# Shutdown_2019_v1_1_BrakeLight.net
KiCad netlist of a schematic drawn in Altium Designer
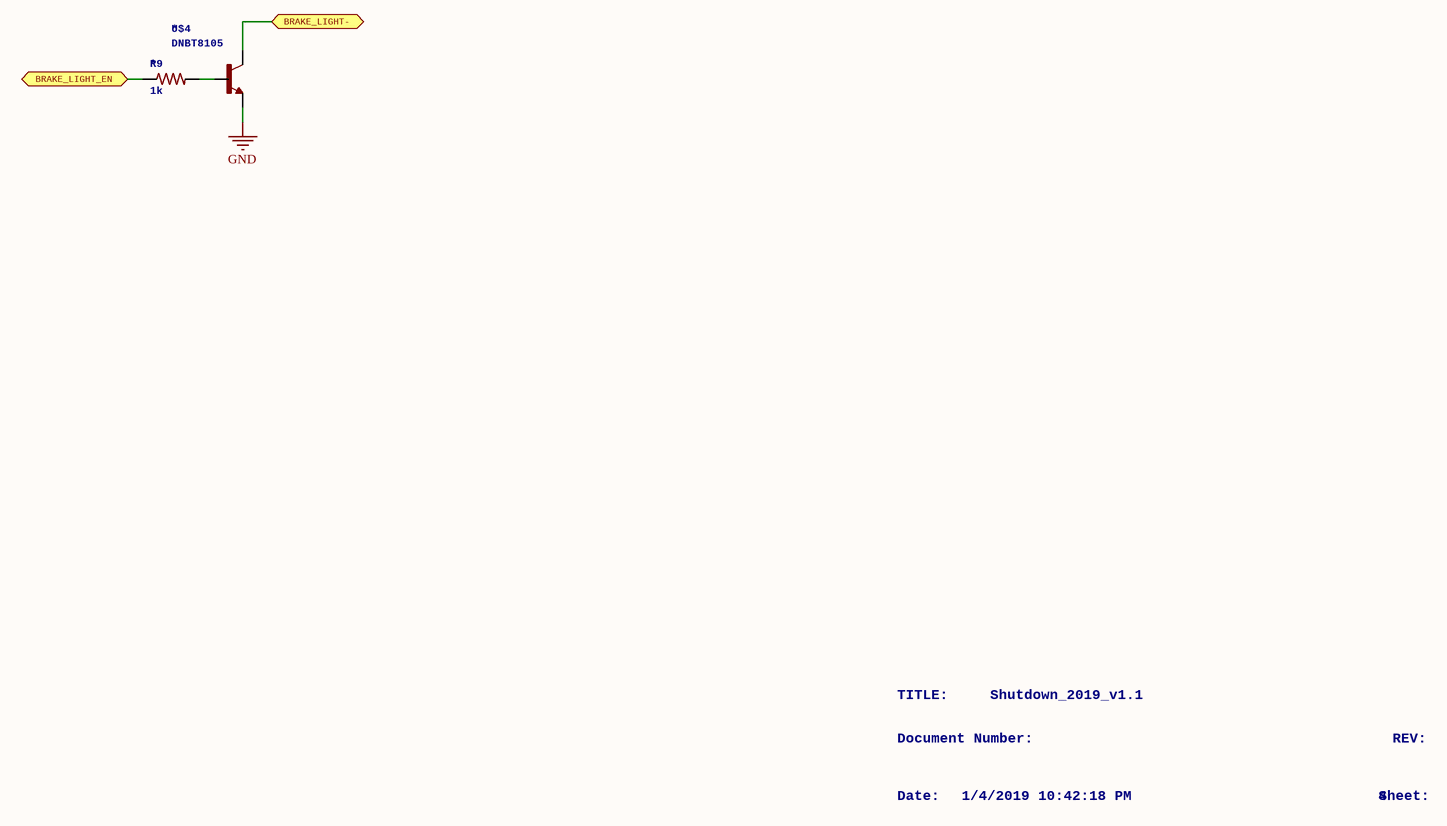
[diagram p0: Shutdown_2019_v1.1_BrakeLight.SchDoc]

(export (version "E")
  (design (tool "Eeschema 10.0.6"))
  (components
    (comp (ref "R9")
      (value "1k")
      (footprint "R0603")
      (description "RESISTOR, American symbol")
      (fields (field (name "NAME") "*"))
      (libsource (lib "rcl") (part "R-US_R0603"))
    )
    (comp (ref "U$4")
      (value "DNBT8105")
      (footprint "SOT23-3")
      (fields (field (name "NAME") "*"))
      (libsource (lib "DIODES_INC") (part "DNBT8105"))
    )
  )
  (nets
    (net (code "1") (name "/BRAKE_LIGHT-") (class "Default")
      (node (ref "U$4") (pin "3") (pinfunction "C_3") (pintype "passive"))
    )
    (net (code "2") (name "/BRAKE_LIGHT_EN") (class "Default")
      (node (ref "R9") (pin "1") (pinfunction "1_1") (pintype "passive"))
    )
    (net (code "3") (name "GND") (class "Default")
      (node (ref "U$4") (pin "2") (pinfunction "E_2") (pintype "passive"))
    )
    (net (code "4") (name "Net-(U$4-B)") (class "Default")
      (node (ref "R9") (pin "2") (pinfunction "2_2") (pintype "passive"))
      (node (ref "U$4") (pin "1") (pinfunction "B_1") (pintype "passive"))
    )
  )
)
